# Reset.net
KiCad netlist of a schematic drawn in Altium Designer
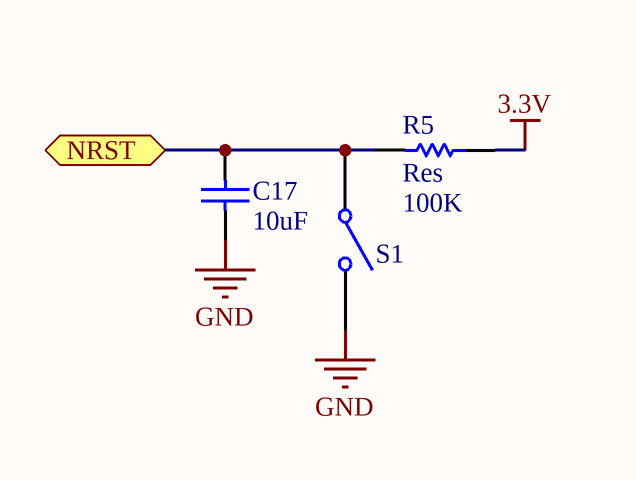
[diagram p0: Reset.SchDoc]

(export (version "E")
  (design (tool "Eeschema 10.0.6"))
  (components
    (comp (ref "C17")
      (value "10uF")
      (footprint "2012[0805]")
      (description "Capacitor")
      (fields (field (name "Comment") "Cap_UP") (field (name "PUBLISHER") "Altium Limited"))
      (libsource (lib "KN2CLib") (part "Cap_UP"))
    )
    (comp (ref "R5")
      (value "Res")
      (footprint "2012[0805]")
      (description "Semiconductor Resistor")
      (fields (field (name "ALTIUM_VALUE") "100K") (field (name "PUBLISHER") "Altium Limited"))
      (libsource (lib "KN2CLib") (part "Res"))
    )
    (comp (ref "S1")
      (value "SW-SPST")
      (footprint "SW-SMD")
      (description "Single-Pole, Single-Throw Switch")
      (fields (field (name "PUBLISHER") "Altium Limited"))
      (libsource (lib "KN2CLib") (part "SW-SPST"))
    )
  )
  (nets
    (net (code "1") (name "/NRST") (class "Default")
      (node (ref "C17") (pin "2") (pinfunction "2_2") (pintype "passive"))
      (node (ref "R5") (pin "2") (pinfunction "2_2") (pintype "passive"))
      (node (ref "S1") (pin "1") (pinfunction "COMMON_1") (pintype "passive"))
    )
    (net (code "2") (name "3.3V") (class "Default")
      (node (ref "R5") (pin "1") (pinfunction "1_1") (pintype "passive"))
    )
    (net (code "3") (name "GND") (class "Default")
      (node (ref "C17") (pin "1") (pinfunction "1_1") (pintype "passive"))
      (node (ref "S1") (pin "2") (pinfunction "NO_2") (pintype "passive"))
    )
  )
)
